# Power_Rev2.net
KiCad netlist of a schematic drawn in Altium Designer
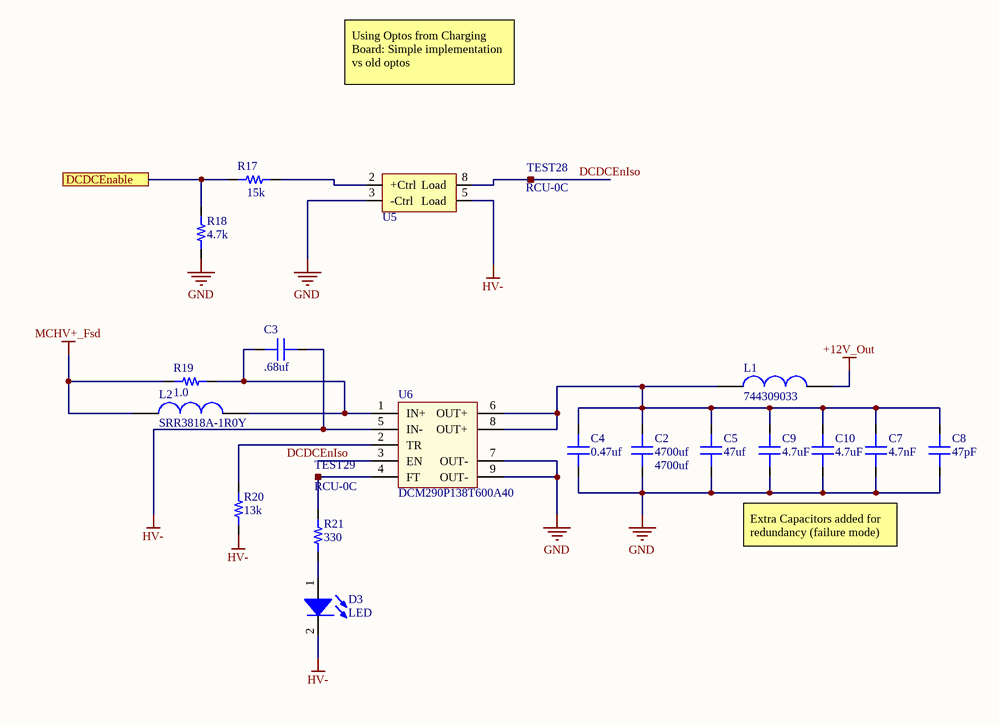
[diagram p0: Power_Rev2.SchDoc]

(export (version "E")
  (design (tool "Eeschema 10.0.6"))
  (components
    (comp (ref "C2")
      (value "4700uf")
      (footprint "CAP AL TH D16 L7.5 H16.5")
      (fields
        (field (name "ALTIUM_VALUE") "4700uf")
        (field (name "TOLERANCE") "20%")
        (field (name "MFRPARTNO") "UVZ1E472MHD")
        (field (name "CREATED_BY") "Angel Delgado")
      )
      (libsource (lib "Altium-Lib") (part "Capacitor"))
    )
    (comp (ref "C3")
      (value ".68uf")
      (footprint "ECW-FD2W684K-TH-CAP")
      (fields
        (field (name "TOLERANCE") "10%")
        (field (name "MFRPARTNO") "ECW-FD2W684K")
        (field (name "Comment") "HV Cap")
        (field (name "CREATED_BY") "Angel Delgado")
      )
      (libsource (lib "Altium-Lib") (part "Capacitor"))
    )
    (comp (ref "C4")
      (value "0.47uf")
      (footprint "CAP 0603/1608")
      (fields
        (field (name "Comment") "Capacitor MLCC 0.47uf 16V CAP 0603/1608")
        (field (name "CREATED_BY") "Nick Mah")
      )
      (libsource (lib "Altium-Lib") (part "Capacitor"))
    )
    (comp (ref "C5")
      (value "47uf")
      (footprint "CAP 0603/1608")
      (fields
        (field (name "Comment") "Capacitor MLCC 47uf 16V CAP 0603/1608")
        (field (name "CREATED_BY") "Nick Mah")
      )
      (libsource (lib "Altium-Lib") (part "Capacitor"))
    )
    (comp (ref "C7")
      (value "4.7nF")
      (footprint "CAP 0603/1608")
      (fields
        (field (name "Comment") "Capacitor MLCC 47uf 16V CAP 0603/1608")
        (field (name "CREATED_BY") "Nick Mah")
      )
      (libsource (lib "Altium-Lib") (part "Capacitor"))
    )
    (comp (ref "C8")
      (value "47pF")
      (footprint "CAP 0603/1608")
      (fields
        (field (name "Comment") "Capacitor MLCC 47uf 16V CAP 0603/1608")
        (field (name "CREATED_BY") "Nick Mah")
      )
      (libsource (lib "Altium-Lib") (part "Capacitor"))
    )
    (comp (ref "C9")
      (value "4.7uF")
      (footprint "CAP 0603/1608")
      (fields
        (field (name "Comment") "Capacitor MLCC 47uf 16V CAP 0603/1608")
        (field (name "CREATED_BY") "Nick Mah")
      )
      (libsource (lib "Altium-Lib") (part "Capacitor"))
    )
    (comp (ref "C10")
      (value "4.7uF")
      (footprint "CAP 0603/1608")
      (fields
        (field (name "Comment") "Capacitor MLCC 47uf 16V CAP 0603/1608")
        (field (name "CREATED_BY") "Nick Mah")
      )
      (libsource (lib "Altium-Lib") (part "Capacitor"))
    )
    (comp (ref "D3") (value "LED") (footprint "0805_LED") (libsource (lib "Altium-Lib") (part "LED")))
    (comp (ref "L1")
      (value "744309033")
      (footprint "744309033")
      (description "330nH wirewound inductor")
      (fields (field (name "CREATED_BY") "Graydon"))
      (libsource (lib "Altium-Lib") (part "744309033"))
    )
    (comp (ref "L2")
      (value "SRR3818A-1R0Y")
      (footprint "SRR3818A-1R0Y")
      (description "1uH fixed inductor")
      (fields (field (name "CREATED_BY") "Graydon"))
      (libsource (lib "Altium-Lib") (part "SRR3818A-1R0Y"))
    )
    (comp (ref "R17")
      (value "15k")
      (footprint "RES 0603/1608")
      (fields
        (field (name "TOLERANCE") "1%")
        (field (name "POWER") "1/10W")
        (field (name "Comment") "Resistor 3.0k 0603 1/10W 1%")
        (field (name "CREATED_BY") "Nick Mah")
      )
      (libsource (lib "Altium-Lib") (part "Resistor"))
    )
    (comp (ref "R18")
      (value "4.7k")
      (footprint "RES 0603/1608")
      (fields
        (field (name "TOLERANCE") "1%")
        (field (name "POWER") "1/10W")
        (field (name "Comment") "Resistor 4.7k 0603 1/10W 1%")
        (field (name "CREATED_BY") "Nick Mah")
      )
      (libsource (lib "Altium-Lib") (part "Resistor"))
    )
    (comp (ref "R19")
      (value "1.0")
      (footprint "RES 0603/1608")
      (fields
        (field (name "TOLERANCE") "1%")
        (field (name "POWER") "1/10W")
        (field (name "Comment") "Resistor 1.0 0603 1/10W 1%")
        (field (name "CREATED_BY") "Nick Mah")
      )
      (libsource (lib "Altium-Lib") (part "Resistor"))
    )
    (comp (ref "R20")
      (value "13k")
      (footprint "RES 0603/1608")
      (fields
        (field (name "TOLERANCE") "1%")
        (field (name "POWER") "1/10W")
        (field (name "Comment") "Resistor 13k 0603 1/10W 1%")
        (field (name "CREATED_BY") "Nick Mah")
      )
      (libsource (lib "Altium-Lib") (part "Resistor"))
    )
    (comp (ref "R21")
      (value "330")
      (footprint "RES 0603/1608")
      (fields
        (field (name "TOLERANCE") "1%")
        (field (name "POWER") "1/10W")
        (field (name "Comment") "Resistor 330 0603 1/10W 1%")
        (field (name "CREATED_BY") "Nick Mah")
      )
      (libsource (lib "Altium-Lib") (part "Resistor"))
    )
    (comp (ref "TEST28")
      (value "RCU-0C")
      (footprint "RCU-0C")
      (description "Test point")
      (fields (field (name "CREATED_BY") "Graydon") (field (name "UPDATED_BY") "Null"))
      (libsource (lib "Altium-Lib") (part "RCU-0C"))
    )
    (comp (ref "TEST29")
      (value "RCU-0C")
      (footprint "RCU-0C")
      (description "Test point")
      (fields (field (name "CREATED_BY") "Graydon") (field (name "UPDATED_BY") "Null"))
      (libsource (lib "Altium-Lib") (part "RCU-0C"))
    )
    (comp (ref "U5")
      (value "SSR NC")
      (footprint "PLB171P")
      (description "Optoisolator: solid state relay, normally closed")
      (fields (field (name "MFRPARTNO") "PLB171P") (field (name "CREATED_BY") "gray"))
      (libsource (lib "Altium-Lib") (part "PLB171"))
    )
    (comp (ref "U6")
      (value "DCM290P138T600A40")
      (footprint "DCM290P138T600A40")
      (description "Vicor DC/DC converter")
      (fields (field (name "CREATED_BY") "Graydon"))
      (libsource (lib "Altium-Lib") (part "DCM290P138T600A40"))
    )
  )
  (nets
    (net (code "1") (name "+12V_Out") (class "Default")
      (node (ref "L1") (pin "2") (pinfunction "2_2") (pintype "power_in"))
    )
    (net (code "2") (name "/DCDCEnIso") (class "Default")
      (node (ref "TEST28") (pin "1") (pintype "passive"))
      (node (ref "U5") (pin "8") (pinfunction "Load_8") (pintype "passive"))
      (node (ref "U6") (pin "3") (pinfunction "EN_3") (pintype "power_in"))
    )
    (net (code "3") (name "/DCDCEnable") (class "Default")
      (node (ref "R17") (pin "1") (pinfunction "1_1") (pintype "passive"))
      (node (ref "R18") (pin "2") (pinfunction "2_2") (pintype "passive"))
    )
    (net (code "4") (name "GND") (class "Default")
      (node (ref "C10") (pin "2") (pinfunction "2_2") (pintype "passive"))
      (node (ref "C2") (pin "2") (pinfunction "2_2") (pintype "passive"))
      (node (ref "C4") (pin "1") (pinfunction "1_1") (pintype "passive"))
      (node (ref "C5") (pin "2") (pinfunction "2_2") (pintype "passive"))
      (node (ref "C7") (pin "2") (pinfunction "2_2") (pintype "passive"))
      (node (ref "C8") (pin "2") (pinfunction "2_2") (pintype "passive"))
      (node (ref "C9") (pin "2") (pinfunction "2_2") (pintype "passive"))
      (node (ref "R18") (pin "1") (pinfunction "1_1") (pintype "passive"))
      (node (ref "U5") (pin "3") (pinfunction "-Ctrl_3") (pintype "passive"))
      (node (ref "U6") (pin "7") (pinfunction "OUT-_7") (pintype "power_in"))
      (node (ref "U6") (pin "9") (pinfunction "OUT-_9") (pintype "power_in"))
    )
    (net (code "5") (name "HV-") (class "Default")
      (node (ref "C3") (pin "1") (pinfunction "1_1") (pintype "passive"))
      (node (ref "D3") (pin "2") (pinfunction "K_2") (pintype "passive"))
      (node (ref "R20") (pin "1") (pinfunction "1_1") (pintype "passive"))
      (node (ref "U5") (pin "5") (pinfunction "Load_5") (pintype "passive"))
      (node (ref "U6") (pin "5") (pinfunction "IN-_5") (pintype "power_in"))
    )
    (net (code "6") (name "MCHV+_Fsd") (class "Default")
      (node (ref "L2") (pin "1") (pintype "power_in"))
      (node (ref "R19") (pin "1") (pinfunction "1_1") (pintype "passive"))
    )
    (net (code "7") (name "Net-(C10-Pad1)") (class "Default")
      (node (ref "C10") (pin "1") (pinfunction "1_1") (pintype "passive"))
      (node (ref "C2") (pin "1") (pinfunction "1_1") (pintype "passive"))
      (node (ref "C4") (pin "2") (pinfunction "2_2") (pintype "passive"))
      (node (ref "C5") (pin "1") (pinfunction "1_1") (pintype "passive"))
      (node (ref "C7") (pin "1") (pinfunction "1_1") (pintype "passive"))
      (node (ref "C8") (pin "1") (pinfunction "1_1") (pintype "passive"))
      (node (ref "C9") (pin "1") (pinfunction "1_1") (pintype "passive"))
      (node (ref "L1") (pin "1") (pintype "power_in"))
      (node (ref "U6") (pin "6") (pinfunction "OUT+_6") (pintype "power_in"))
      (node (ref "U6") (pin "8") (pinfunction "OUT+_8") (pintype "power_in"))
    )
    (net (code "8") (name "Net-(D3-A)") (class "Default")
      (node (ref "D3") (pin "1") (pinfunction "A_1") (pintype "passive"))
      (node (ref "R21") (pin "1") (pinfunction "1_1") (pintype "passive"))
    )
    (net (code "9") (name "Net-(U5-+Ctrl)") (class "Default")
      (node (ref "R17") (pin "2") (pinfunction "2_2") (pintype "passive"))
      (node (ref "U5") (pin "2") (pinfunction "+Ctrl_2") (pintype "passive"))
    )
    (net (code "10") (name "Net-(U6-FT)") (class "Default")
      (node (ref "R21") (pin "2") (pinfunction "2_2") (pintype "passive"))
      (node (ref "TEST29") (pin "1") (pintype "passive"))
      (node (ref "U6") (pin "4") (pinfunction "FT_4") (pintype "power_in"))
    )
    (net (code "11") (name "Net-(U6-IN+)") (class "Default")
      (node (ref "C3") (pin "2") (pinfunction "2_2") (pintype "passive"))
      (node (ref "L2") (pin "2") (pinfunction "2_2") (pintype "power_in"))
      (node (ref "R19") (pin "2") (pinfunction "2_2") (pintype "passive"))
      (node (ref "U6") (pin "1") (pinfunction "IN+_1") (pintype "power_in"))
    )
    (net (code "12") (name "Net-(U6-TR)") (class "Default")
      (node (ref "R20") (pin "2") (pinfunction "2_2") (pintype "passive"))
      (node (ref "U6") (pin "2") (pinfunction "TR_2") (pintype "power_in"))
    )
  )
)
